# LED8_15.net
KiCad netlist of a schematic drawn in Altium Designer
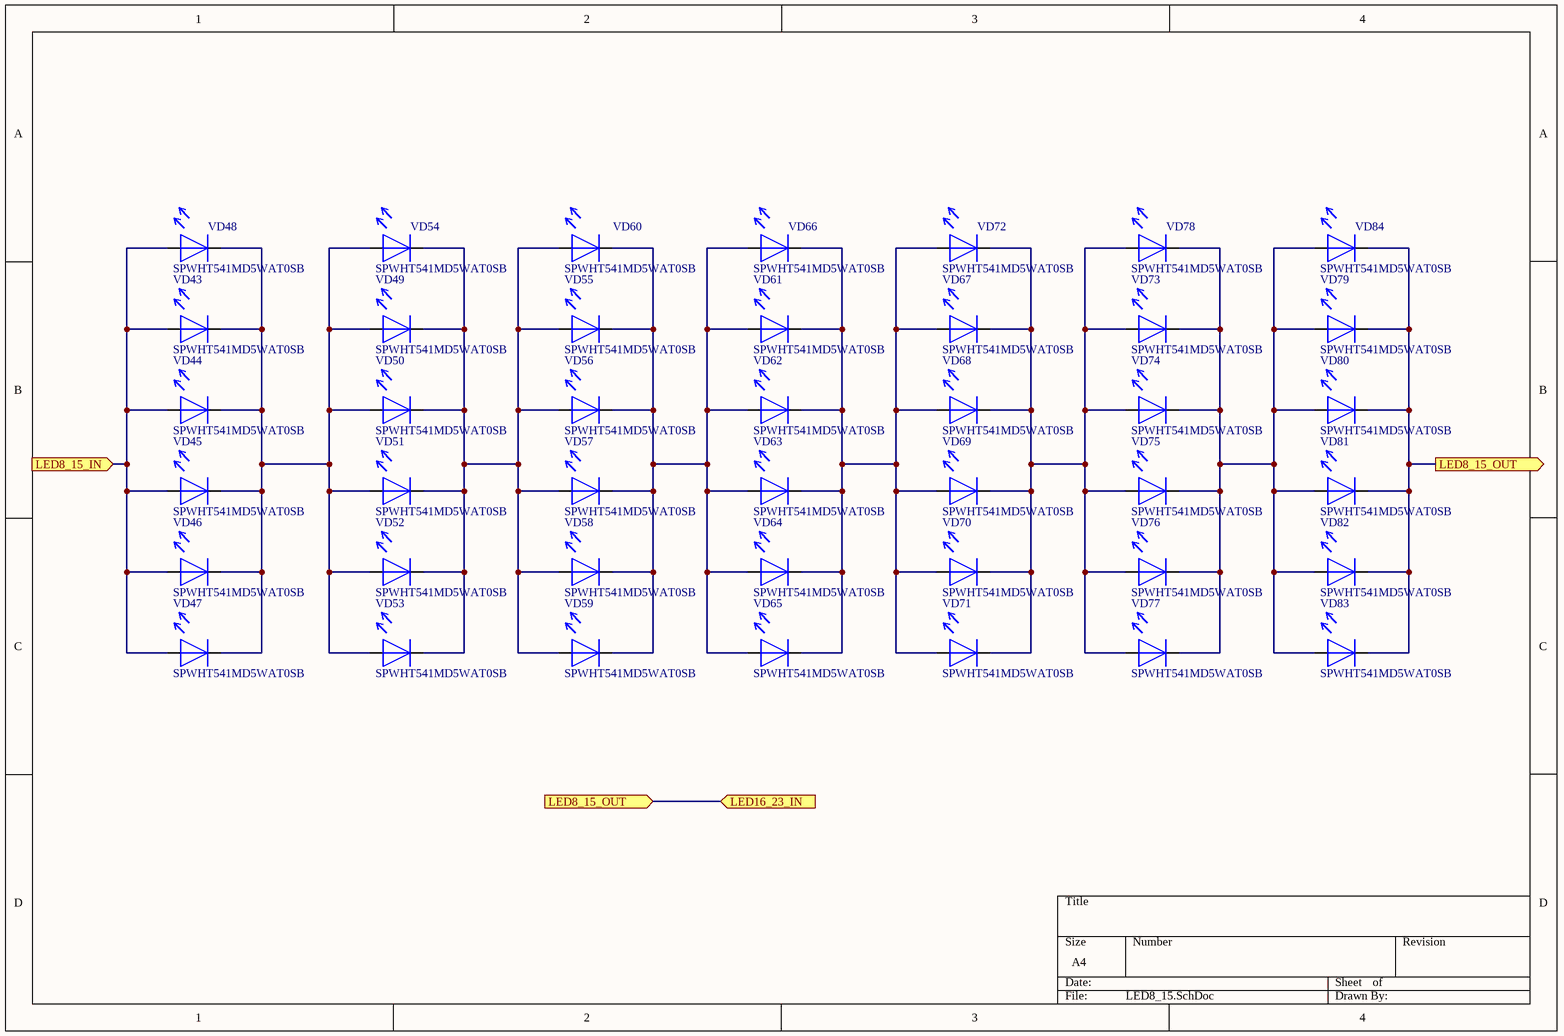
[diagram p0: LED8_15.SchDoc]

(export (version "E")
  (design (tool "Eeschema 10.0.6"))
  (components
    (comp (ref "VD43")
      (value "SPWHT541MD5WAT0SB")
      (footprint "LED_SAMSUNG")
      (libsource (lib "gprs_modem") (part "LED SPWHT541MD5WAT0SB"))
    )
    (comp (ref "VD44")
      (value "SPWHT541MD5WAT0SB")
      (footprint "LED_SAMSUNG")
      (libsource (lib "gprs_modem") (part "LED SPWHT541MD5WAT0SB"))
    )
    (comp (ref "VD45")
      (value "SPWHT541MD5WAT0SB")
      (footprint "LED_SAMSUNG")
      (libsource (lib "gprs_modem") (part "LED SPWHT541MD5WAT0SB"))
    )
    (comp (ref "VD46")
      (value "SPWHT541MD5WAT0SB")
      (footprint "LED_SAMSUNG")
      (libsource (lib "gprs_modem") (part "LED SPWHT541MD5WAT0SB"))
    )
    (comp (ref "VD47")
      (value "SPWHT541MD5WAT0SB")
      (footprint "LED_SAMSUNG")
      (libsource (lib "gprs_modem") (part "LED SPWHT541MD5WAT0SB"))
    )
    (comp (ref "VD48")
      (value "SPWHT541MD5WAT0SB")
      (footprint "LED_SAMSUNG")
      (libsource (lib "gprs_modem") (part "LED SPWHT541MD5WAT0SB"))
    )
    (comp (ref "VD49")
      (value "SPWHT541MD5WAT0SB")
      (footprint "LED_SAMSUNG")
      (libsource (lib "gprs_modem") (part "LED SPWHT541MD5WAT0SB"))
    )
    (comp (ref "VD50")
      (value "SPWHT541MD5WAT0SB")
      (footprint "LED_SAMSUNG")
      (libsource (lib "gprs_modem") (part "LED SPWHT541MD5WAT0SB"))
    )
    (comp (ref "VD51")
      (value "SPWHT541MD5WAT0SB")
      (footprint "LED_SAMSUNG")
      (libsource (lib "gprs_modem") (part "LED SPWHT541MD5WAT0SB"))
    )
    (comp (ref "VD52")
      (value "SPWHT541MD5WAT0SB")
      (footprint "LED_SAMSUNG")
      (libsource (lib "gprs_modem") (part "LED SPWHT541MD5WAT0SB"))
    )
    (comp (ref "VD53")
      (value "SPWHT541MD5WAT0SB")
      (footprint "LED_SAMSUNG")
      (libsource (lib "gprs_modem") (part "LED SPWHT541MD5WAT0SB"))
    )
    (comp (ref "VD54")
      (value "SPWHT541MD5WAT0SB")
      (footprint "LED_SAMSUNG")
      (libsource (lib "gprs_modem") (part "LED SPWHT541MD5WAT0SB"))
    )
    (comp (ref "VD55")
      (value "SPWHT541MD5WAT0SB")
      (footprint "LED_SAMSUNG")
      (libsource (lib "gprs_modem") (part "LED SPWHT541MD5WAT0SB"))
    )
    (comp (ref "VD56")
      (value "SPWHT541MD5WAT0SB")
      (footprint "LED_SAMSUNG")
      (libsource (lib "gprs_modem") (part "LED SPWHT541MD5WAT0SB"))
    )
    (comp (ref "VD57")
      (value "SPWHT541MD5WAT0SB")
      (footprint "LED_SAMSUNG")
      (libsource (lib "gprs_modem") (part "LED SPWHT541MD5WAT0SB"))
    )
    (comp (ref "VD58")
      (value "SPWHT541MD5WAT0SB")
      (footprint "LED_SAMSUNG")
      (libsource (lib "gprs_modem") (part "LED SPWHT541MD5WAT0SB"))
    )
    (comp (ref "VD59")
      (value "SPWHT541MD5WAT0SB")
      (footprint "LED_SAMSUNG")
      (libsource (lib "gprs_modem") (part "LED SPWHT541MD5WAT0SB"))
    )
    (comp (ref "VD60")
      (value "SPWHT541MD5WAT0SB")
      (footprint "LED_SAMSUNG")
      (libsource (lib "gprs_modem") (part "LED SPWHT541MD5WAT0SB"))
    )
    (comp (ref "VD61")
      (value "SPWHT541MD5WAT0SB")
      (footprint "LED_SAMSUNG")
      (libsource (lib "gprs_modem") (part "LED SPWHT541MD5WAT0SB"))
    )
    (comp (ref "VD62")
      (value "SPWHT541MD5WAT0SB")
      (footprint "LED_SAMSUNG")
      (libsource (lib "gprs_modem") (part "LED SPWHT541MD5WAT0SB"))
    )
    (comp (ref "VD63")
      (value "SPWHT541MD5WAT0SB")
      (footprint "LED_SAMSUNG")
      (libsource (lib "gprs_modem") (part "LED SPWHT541MD5WAT0SB"))
    )
    (comp (ref "VD64")
      (value "SPWHT541MD5WAT0SB")
      (footprint "LED_SAMSUNG")
      (libsource (lib "gprs_modem") (part "LED SPWHT541MD5WAT0SB"))
    )
    (comp (ref "VD65")
      (value "SPWHT541MD5WAT0SB")
      (footprint "LED_SAMSUNG")
      (libsource (lib "gprs_modem") (part "LED SPWHT541MD5WAT0SB"))
    )
    (comp (ref "VD66")
      (value "SPWHT541MD5WAT0SB")
      (footprint "LED_SAMSUNG")
      (libsource (lib "gprs_modem") (part "LED SPWHT541MD5WAT0SB"))
    )
    (comp (ref "VD67")
      (value "SPWHT541MD5WAT0SB")
      (footprint "LED_SAMSUNG")
      (libsource (lib "gprs_modem") (part "LED SPWHT541MD5WAT0SB"))
    )
    (comp (ref "VD68")
      (value "SPWHT541MD5WAT0SB")
      (footprint "LED_SAMSUNG")
      (libsource (lib "gprs_modem") (part "LED SPWHT541MD5WAT0SB"))
    )
    (comp (ref "VD69")
      (value "SPWHT541MD5WAT0SB")
      (footprint "LED_SAMSUNG")
      (libsource (lib "gprs_modem") (part "LED SPWHT541MD5WAT0SB"))
    )
    (comp (ref "VD70")
      (value "SPWHT541MD5WAT0SB")
      (footprint "LED_SAMSUNG")
      (libsource (lib "gprs_modem") (part "LED SPWHT541MD5WAT0SB"))
    )
    (comp (ref "VD71")
      (value "SPWHT541MD5WAT0SB")
      (footprint "LED_SAMSUNG")
      (libsource (lib "gprs_modem") (part "LED SPWHT541MD5WAT0SB"))
    )
    (comp (ref "VD72")
      (value "SPWHT541MD5WAT0SB")
      (footprint "LED_SAMSUNG")
      (libsource (lib "gprs_modem") (part "LED SPWHT541MD5WAT0SB"))
    )
    (comp (ref "VD73")
      (value "SPWHT541MD5WAT0SB")
      (footprint "LED_SAMSUNG")
      (libsource (lib "gprs_modem") (part "LED SPWHT541MD5WAT0SB"))
    )
    (comp (ref "VD74")
      (value "SPWHT541MD5WAT0SB")
      (footprint "LED_SAMSUNG")
      (libsource (lib "gprs_modem") (part "LED SPWHT541MD5WAT0SB"))
    )
    (comp (ref "VD75")
      (value "SPWHT541MD5WAT0SB")
      (footprint "LED_SAMSUNG")
      (libsource (lib "gprs_modem") (part "LED SPWHT541MD5WAT0SB"))
    )
    (comp (ref "VD76")
      (value "SPWHT541MD5WAT0SB")
      (footprint "LED_SAMSUNG")
      (libsource (lib "gprs_modem") (part "LED SPWHT541MD5WAT0SB"))
    )
    (comp (ref "VD77")
      (value "SPWHT541MD5WAT0SB")
      (footprint "LED_SAMSUNG")
      (libsource (lib "gprs_modem") (part "LED SPWHT541MD5WAT0SB"))
    )
    (comp (ref "VD78")
      (value "SPWHT541MD5WAT0SB")
      (footprint "LED_SAMSUNG")
      (libsource (lib "gprs_modem") (part "LED SPWHT541MD5WAT0SB"))
    )
    (comp (ref "VD79")
      (value "SPWHT541MD5WAT0SB")
      (footprint "LED_SAMSUNG")
      (libsource (lib "gprs_modem") (part "LED SPWHT541MD5WAT0SB"))
    )
    (comp (ref "VD80")
      (value "SPWHT541MD5WAT0SB")
      (footprint "LED_SAMSUNG")
      (libsource (lib "gprs_modem") (part "LED SPWHT541MD5WAT0SB"))
    )
    (comp (ref "VD81")
      (value "SPWHT541MD5WAT0SB")
      (footprint "LED_SAMSUNG")
      (libsource (lib "gprs_modem") (part "LED SPWHT541MD5WAT0SB"))
    )
    (comp (ref "VD82")
      (value "SPWHT541MD5WAT0SB")
      (footprint "LED_SAMSUNG")
      (libsource (lib "gprs_modem") (part "LED SPWHT541MD5WAT0SB"))
    )
    (comp (ref "VD83")
      (value "SPWHT541MD5WAT0SB")
      (footprint "LED_SAMSUNG")
      (libsource (lib "gprs_modem") (part "LED SPWHT541MD5WAT0SB"))
    )
    (comp (ref "VD84")
      (value "SPWHT541MD5WAT0SB")
      (footprint "LED_SAMSUNG")
      (libsource (lib "gprs_modem") (part "LED SPWHT541MD5WAT0SB"))
    )
  )
  (nets
    (net (code "1") (name "/LED8_15_IN") (class "Default")
      (node (ref "VD43") (pin "1") (pintype "passive"))
      (node (ref "VD44") (pin "1") (pintype "passive"))
      (node (ref "VD45") (pin "1") (pintype "passive"))
      (node (ref "VD46") (pin "1") (pintype "passive"))
      (node (ref "VD47") (pin "1") (pintype "passive"))
      (node (ref "VD48") (pin "1") (pintype "passive"))
    )
    (net (code "2") (name "/LED16_23_IN") (class "Default")
      (node (ref "VD79") (pin "2") (pintype "passive"))
      (node (ref "VD80") (pin "2") (pintype "passive"))
      (node (ref "VD81") (pin "2") (pintype "passive"))
      (node (ref "VD82") (pin "2") (pintype "passive"))
      (node (ref "VD83") (pin "2") (pintype "passive"))
      (node (ref "VD84") (pin "2") (pintype "passive"))
    )
    (net (code "3") (name "Net-(VD43-Pad2)") (class "Default")
      (node (ref "VD43") (pin "2") (pintype "passive"))
      (node (ref "VD44") (pin "2") (pintype "passive"))
      (node (ref "VD45") (pin "2") (pintype "passive"))
      (node (ref "VD46") (pin "2") (pintype "passive"))
      (node (ref "VD47") (pin "2") (pintype "passive"))
      (node (ref "VD48") (pin "2") (pintype "passive"))
      (node (ref "VD49") (pin "1") (pintype "passive"))
      (node (ref "VD50") (pin "1") (pintype "passive"))
      (node (ref "VD51") (pin "1") (pintype "passive"))
      (node (ref "VD52") (pin "1") (pintype "passive"))
      (node (ref "VD53") (pin "1") (pintype "passive"))
      (node (ref "VD54") (pin "1") (pintype "passive"))
    )
    (net (code "4") (name "Net-(VD49-Pad2)") (class "Default")
      (node (ref "VD49") (pin "2") (pintype "passive"))
      (node (ref "VD50") (pin "2") (pintype "passive"))
      (node (ref "VD51") (pin "2") (pintype "passive"))
      (node (ref "VD52") (pin "2") (pintype "passive"))
      (node (ref "VD53") (pin "2") (pintype "passive"))
      (node (ref "VD54") (pin "2") (pintype "passive"))
      (node (ref "VD55") (pin "1") (pintype "passive"))
      (node (ref "VD56") (pin "1") (pintype "passive"))
      (node (ref "VD57") (pin "1") (pintype "passive"))
      (node (ref "VD58") (pin "1") (pintype "passive"))
      (node (ref "VD59") (pin "1") (pintype "passive"))
      (node (ref "VD60") (pin "1") (pintype "passive"))
    )
    (net (code "5") (name "Net-(VD55-Pad2)") (class "Default")
      (node (ref "VD55") (pin "2") (pintype "passive"))
      (node (ref "VD56") (pin "2") (pintype "passive"))
      (node (ref "VD57") (pin "2") (pintype "passive"))
      (node (ref "VD58") (pin "2") (pintype "passive"))
      (node (ref "VD59") (pin "2") (pintype "passive"))
      (node (ref "VD60") (pin "2") (pintype "passive"))
      (node (ref "VD61") (pin "1") (pintype "passive"))
      (node (ref "VD62") (pin "1") (pintype "passive"))
      (node (ref "VD63") (pin "1") (pintype "passive"))
      (node (ref "VD64") (pin "1") (pintype "passive"))
      (node (ref "VD65") (pin "1") (pintype "passive"))
      (node (ref "VD66") (pin "1") (pintype "passive"))
    )
    (net (code "6") (name "Net-(VD61-Pad2)") (class "Default")
      (node (ref "VD61") (pin "2") (pintype "passive"))
      (node (ref "VD62") (pin "2") (pintype "passive"))
      (node (ref "VD63") (pin "2") (pintype "passive"))
      (node (ref "VD64") (pin "2") (pintype "passive"))
      (node (ref "VD65") (pin "2") (pintype "passive"))
      (node (ref "VD66") (pin "2") (pintype "passive"))
      (node (ref "VD67") (pin "1") (pintype "passive"))
      (node (ref "VD68") (pin "1") (pintype "passive"))
      (node (ref "VD69") (pin "1") (pintype "passive"))
      (node (ref "VD70") (pin "1") (pintype "passive"))
      (node (ref "VD71") (pin "1") (pintype "passive"))
      (node (ref "VD72") (pin "1") (pintype "passive"))
    )
    (net (code "7") (name "Net-(VD67-Pad2)") (class "Default")
      (node (ref "VD67") (pin "2") (pintype "passive"))
      (node (ref "VD68") (pin "2") (pintype "passive"))
      (node (ref "VD69") (pin "2") (pintype "passive"))
      (node (ref "VD70") (pin "2") (pintype "passive"))
      (node (ref "VD71") (pin "2") (pintype "passive"))
      (node (ref "VD72") (pin "2") (pintype "passive"))
      (node (ref "VD73") (pin "1") (pintype "passive"))
      (node (ref "VD74") (pin "1") (pintype "passive"))
      (node (ref "VD75") (pin "1") (pintype "passive"))
      (node (ref "VD76") (pin "1") (pintype "passive"))
      (node (ref "VD77") (pin "1") (pintype "passive"))
      (node (ref "VD78") (pin "1") (pintype "passive"))
    )
    (net (code "8") (name "Net-(VD73-Pad2)") (class "Default")
      (node (ref "VD73") (pin "2") (pintype "passive"))
      (node (ref "VD74") (pin "2") (pintype "passive"))
      (node (ref "VD75") (pin "2") (pintype "passive"))
      (node (ref "VD76") (pin "2") (pintype "passive"))
      (node (ref "VD77") (pin "2") (pintype "passive"))
      (node (ref "VD78") (pin "2") (pintype "passive"))
      (node (ref "VD79") (pin "1") (pintype "passive"))
      (node (ref "VD80") (pin "1") (pintype "passive"))
      (node (ref "VD81") (pin "1") (pintype "passive"))
      (node (ref "VD82") (pin "1") (pintype "passive"))
      (node (ref "VD83") (pin "1") (pintype "passive"))
      (node (ref "VD84") (pin "1") (pintype "passive"))
    )
  )
)
